# moscow_esp8266_revb.net
KiCad netlist of a schematic drawn in EAGLE
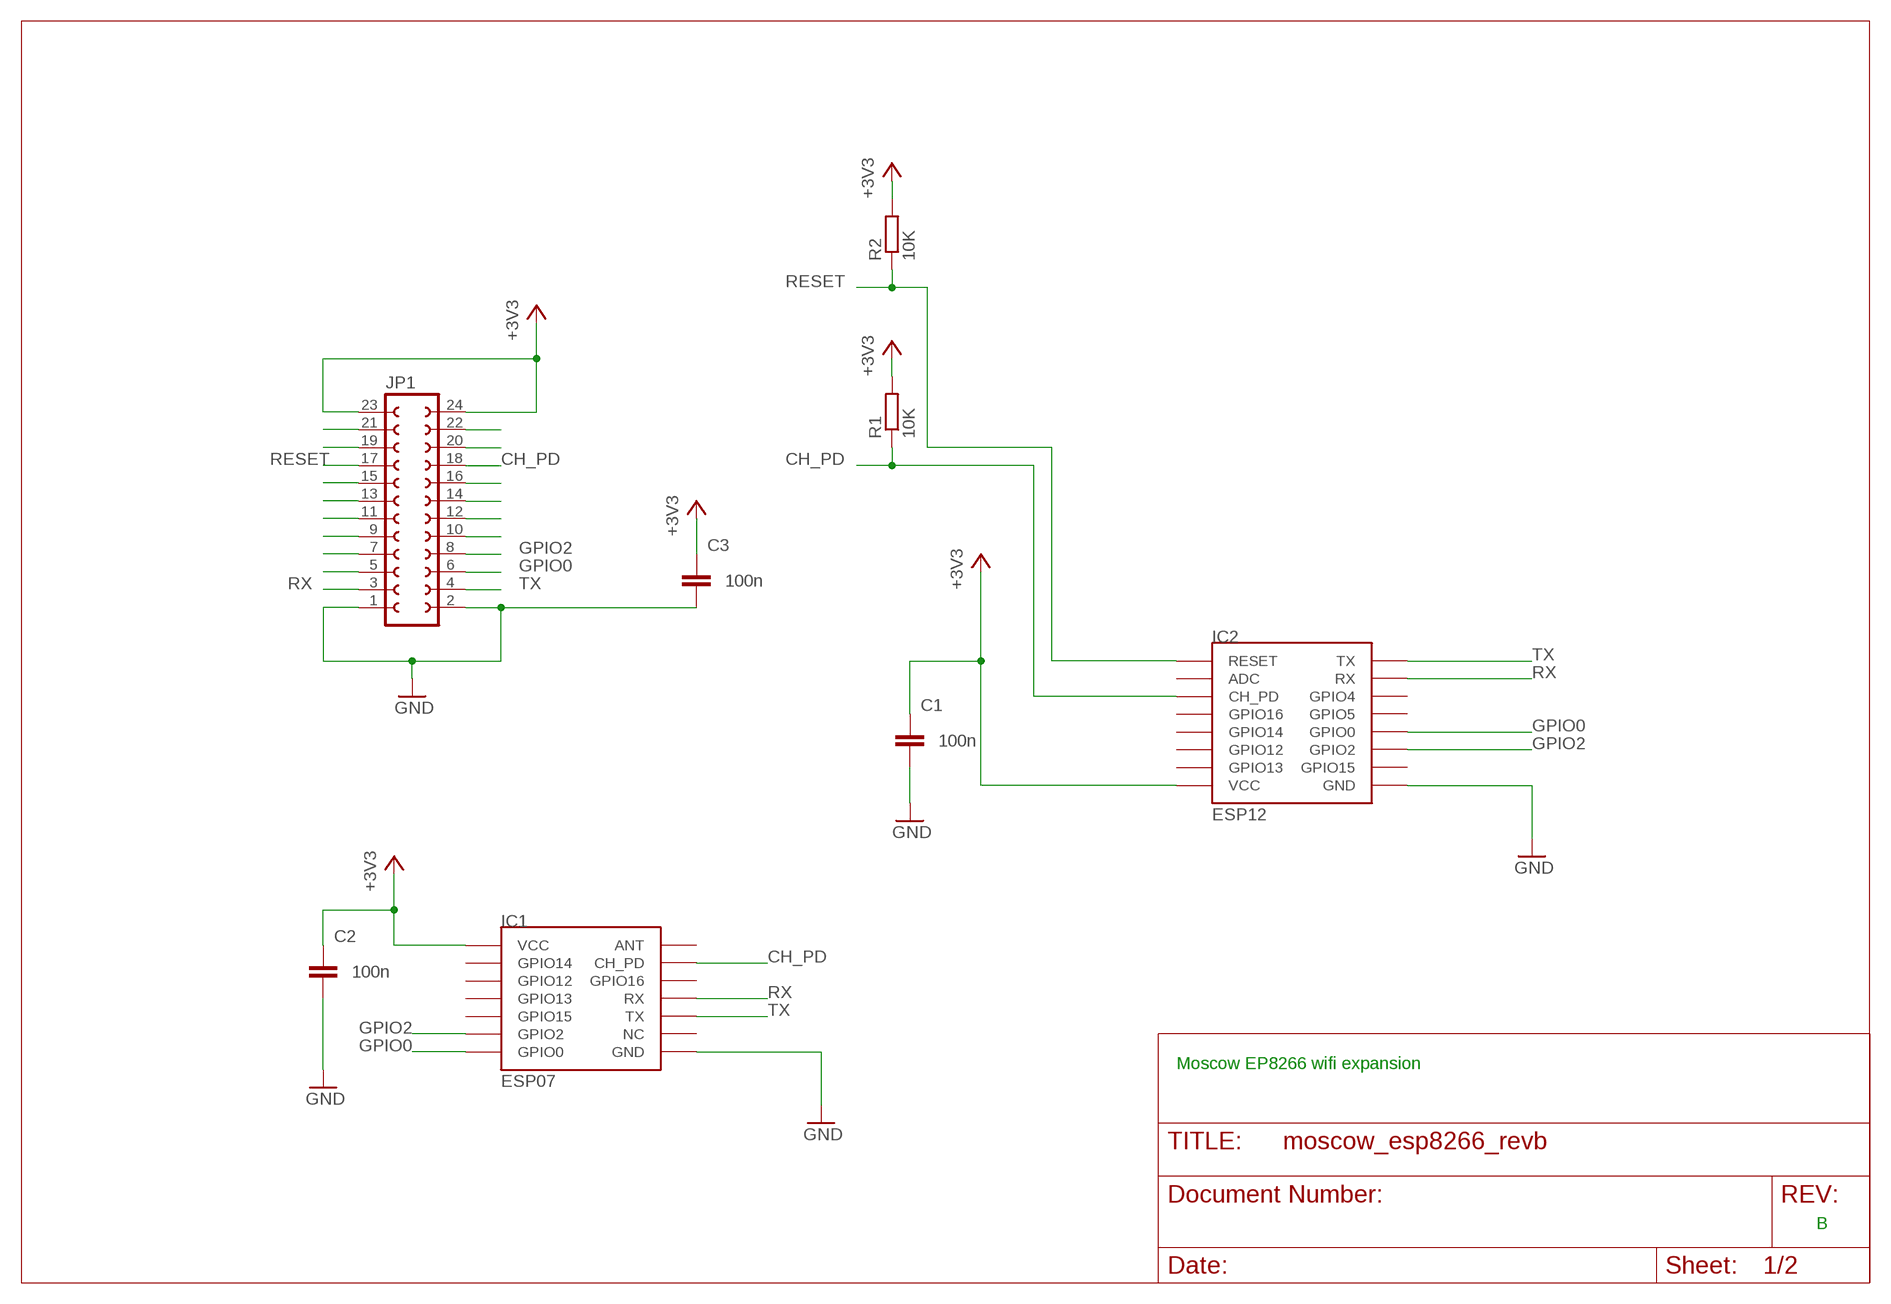
[diagram p0: schematic, sheet 1]
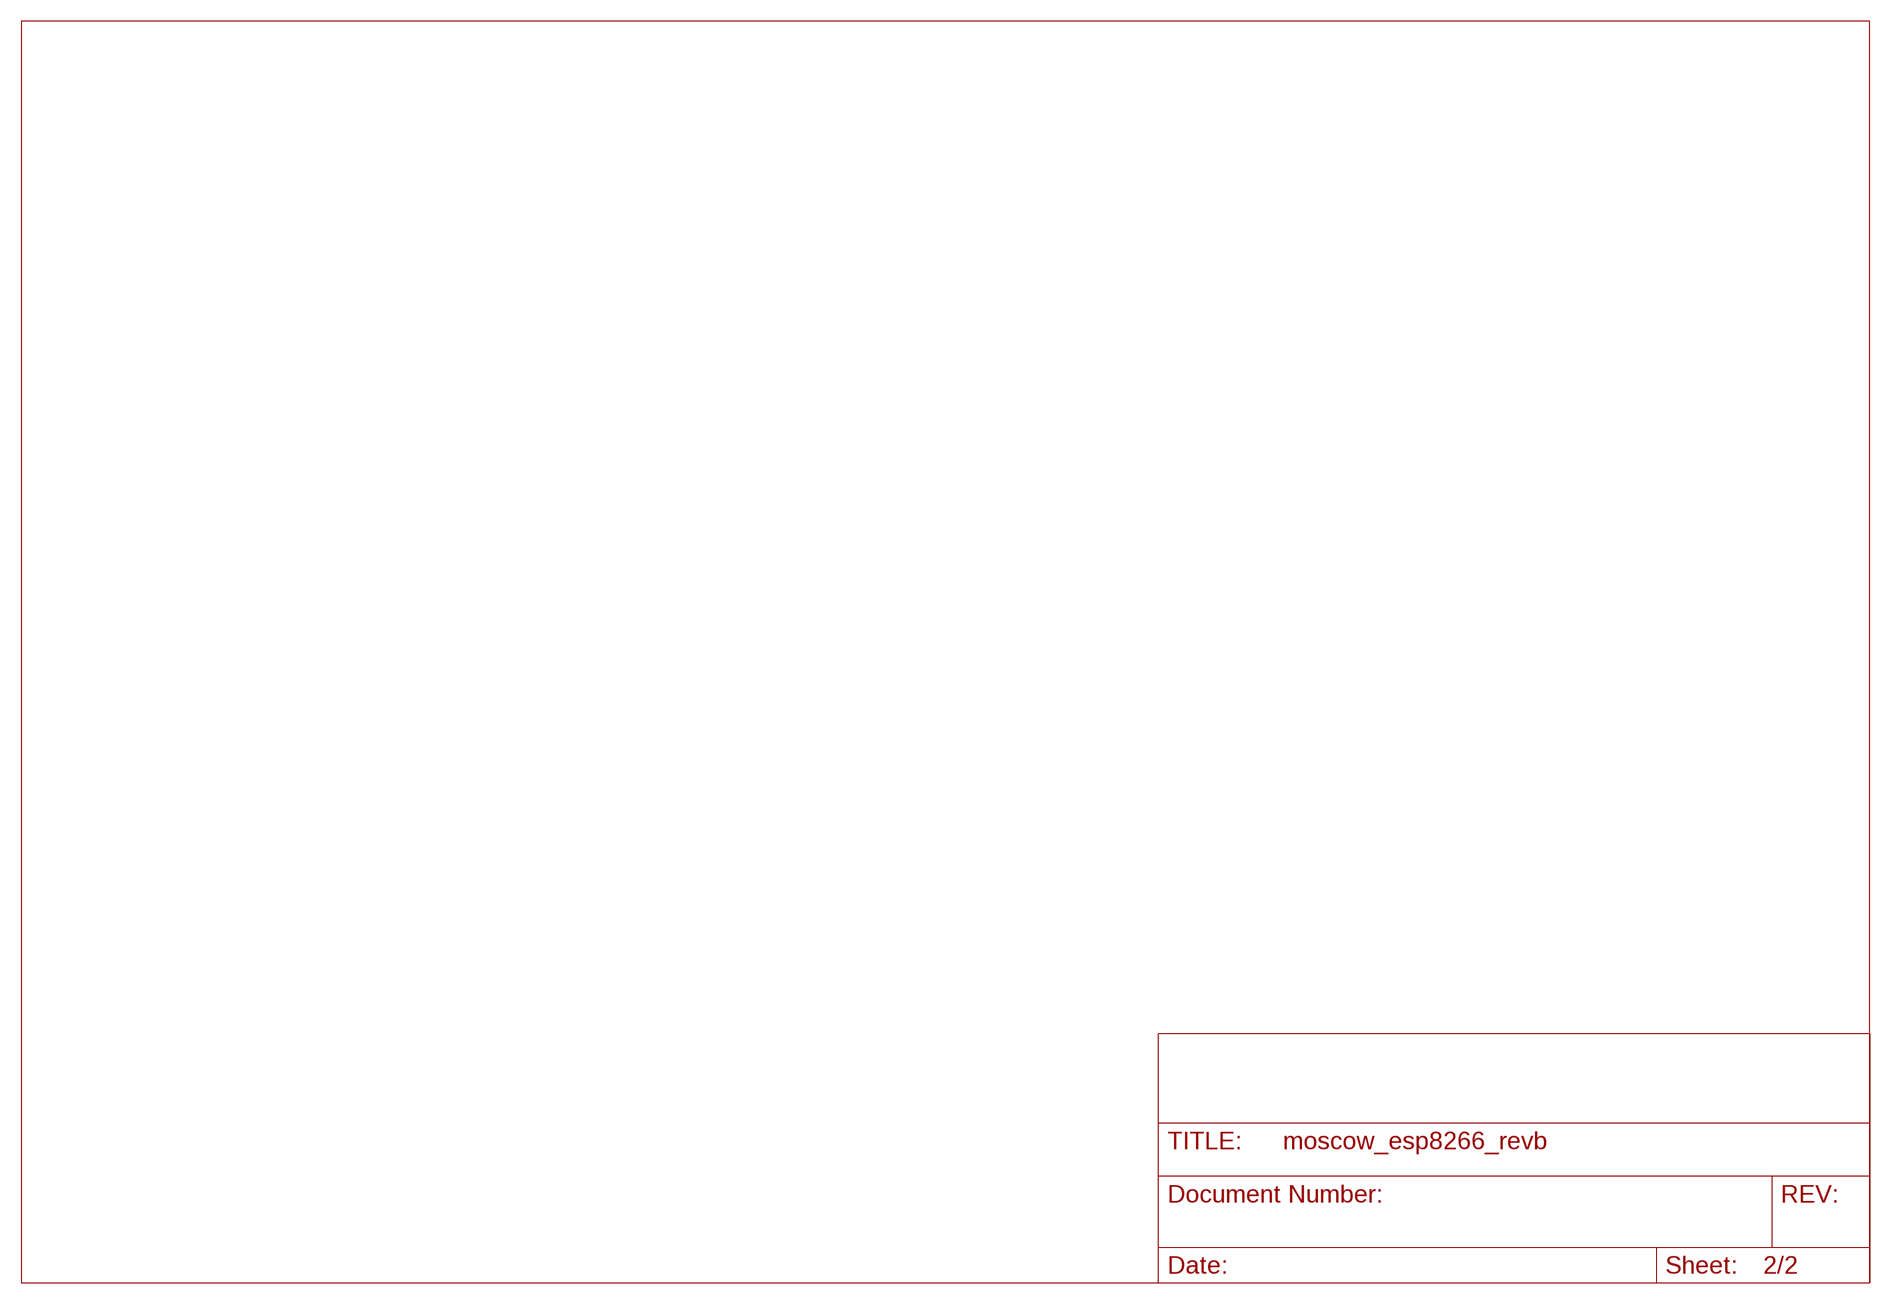
[diagram p1: schematic, sheet 2]

(export (version "E")
  (design (tool "Eeschema 10.0.6"))
  (components
    (comp (ref "C1")
      (value "100n")
      (footprint "eagle-import:C0805")
      (libsource (lib "eagle-import") (part "C-EUC0805"))
    )
    (comp (ref "C2")
      (value "100n")
      (footprint "eagle-import:C0805")
      (libsource (lib "eagle-import") (part "C-EUC0805"))
    )
    (comp (ref "C3")
      (value "100n")
      (footprint "eagle-import:C0805")
      (libsource (lib "eagle-import") (part "C-EUC0805"))
    )
    (comp (ref "IC1")
      (value "ESP07")
      (footprint "eagle-import:ESP07")
      (libsource (lib "eagle-import") (part "ESP07"))
    )
    (comp (ref "IC2")
      (value "ESP12")
      (footprint "eagle-import:ESP12")
      (libsource (lib "eagle-import") (part "ESP12"))
    )
    (comp (ref "JP1")
      (value "FE12-2")
      (footprint "eagle-import:FE12-2")
      (libsource (lib "eagle-import") (part "FE12-2"))
    )
    (comp (ref "R1")
      (value "10K")
      (footprint "eagle-import:R0805")
      (libsource (lib "eagle-import") (part "R-EU_R0805"))
    )
    (comp (ref "R2")
      (value "10K")
      (footprint "eagle-import:R0805")
      (libsource (lib "eagle-import") (part "R-EU_R0805"))
    )
  )
  (nets
    (net (code "1") (name "+3V3") (class "Default")
      (node (ref "C1") (pin "1") (pinfunction "1_1") (pintype "passive"))
      (node (ref "C2") (pin "1") (pinfunction "1_1") (pintype "passive"))
      (node (ref "C3") (pin "1") (pinfunction "1_1") (pintype "passive"))
      (node (ref "IC1") (pin "VCC") (pinfunction "VCC_VCC") (pintype "bidirectional"))
      (node (ref "IC2") (pin "VCC") (pinfunction "VCC_VCC") (pintype "bidirectional"))
      (node (ref "JP1") (pin "23") (pinfunction "23_23") (pintype "passive"))
      (node (ref "JP1") (pin "24") (pinfunction "24_24") (pintype "passive"))
      (node (ref "R1") (pin "2") (pinfunction "2_2") (pintype "passive"))
      (node (ref "R2") (pin "2") (pinfunction "2_2") (pintype "passive"))
    )
    (net (code "2") (name "CH_PD") (class "Default")
      (node (ref "IC1") (pin "CH_PD") (pinfunction "CH_PD_CH_PD") (pintype "bidirectional"))
      (node (ref "IC2") (pin "CH_PD") (pinfunction "CH_PD_CH_PD") (pintype "bidirectional"))
      (node (ref "JP1") (pin "18") (pinfunction "18_18") (pintype "passive"))
      (node (ref "R1") (pin "1") (pinfunction "1_1") (pintype "passive"))
    )
    (net (code "3") (name "GND") (class "Default")
      (node (ref "C1") (pin "2") (pinfunction "2_2") (pintype "passive"))
      (node (ref "C2") (pin "2") (pinfunction "2_2") (pintype "passive"))
      (node (ref "C3") (pin "2") (pinfunction "2_2") (pintype "passive"))
      (node (ref "IC1") (pin "GND") (pinfunction "GND_GND") (pintype "bidirectional"))
      (node (ref "IC2") (pin "GND") (pinfunction "GND_GND") (pintype "bidirectional"))
      (node (ref "JP1") (pin "1") (pinfunction "1_1") (pintype "passive"))
      (node (ref "JP1") (pin "2") (pinfunction "2_2") (pintype "passive"))
    )
    (net (code "4") (name "GPIO0") (class "Default")
      (node (ref "IC1") (pin "GPIO0") (pinfunction "GPIO0_GPIO0") (pintype "bidirectional"))
      (node (ref "IC2") (pin "GPIO0") (pinfunction "GPIO0_GPIO0") (pintype "bidirectional"))
      (node (ref "JP1") (pin "6") (pinfunction "6_6") (pintype "passive"))
    )
    (net (code "5") (name "GPIO2") (class "Default")
      (node (ref "IC1") (pin "GPIO2") (pinfunction "GPIO2_GPIO2") (pintype "bidirectional"))
      (node (ref "IC2") (pin "GPIO2") (pinfunction "GPIO2_GPIO2") (pintype "bidirectional"))
      (node (ref "JP1") (pin "8") (pinfunction "8_8") (pintype "passive"))
    )
    (net (code "6") (name "RESET") (class "Default")
      (node (ref "IC2") (pin "RESET") (pinfunction "RESET_RESET") (pintype "bidirectional"))
      (node (ref "JP1") (pin "17") (pinfunction "17_17") (pintype "passive"))
      (node (ref "R2") (pin "1") (pinfunction "1_1") (pintype "passive"))
    )
    (net (code "7") (name "RX") (class "Default")
      (node (ref "IC1") (pin "RX") (pinfunction "RX_RX") (pintype "bidirectional"))
      (node (ref "IC2") (pin "RX") (pinfunction "RX_RX") (pintype "bidirectional"))
      (node (ref "JP1") (pin "3") (pinfunction "3_3") (pintype "passive"))
    )
    (net (code "8") (name "TX") (class "Default")
      (node (ref "IC1") (pin "TX") (pinfunction "TX_TX") (pintype "bidirectional"))
      (node (ref "IC2") (pin "TX") (pinfunction "TX_TX") (pintype "bidirectional"))
      (node (ref "JP1") (pin "4") (pinfunction "4_4") (pintype "passive"))
    )
    (net (code "9") (name "unconnected-(IC1-PadANT)") (class "Default")
      (node (ref "IC1") (pin "ANT") (pinfunction "ANT_ANT") (pintype "bidirectional"))
    )
    (net (code "10") (name "unconnected-(IC1-PadGPIO12)") (class "Default")
      (node (ref "IC1") (pin "GPIO12") (pinfunction "GPIO12_GPIO12") (pintype "bidirectional"))
    )
    (net (code "11") (name "unconnected-(IC1-PadGPIO13)") (class "Default")
      (node (ref "IC1") (pin "GPIO13") (pinfunction "GPIO13_GPIO13") (pintype "bidirectional"))
    )
    (net (code "12") (name "unconnected-(IC1-PadGPIO14)") (class "Default")
      (node (ref "IC1") (pin "GPIO14") (pinfunction "GPIO14_GPIO14") (pintype "bidirectional"))
    )
    (net (code "13") (name "unconnected-(IC1-PadGPIO15)") (class "Default")
      (node (ref "IC1") (pin "GPIO15") (pinfunction "GPIO15_GPIO15") (pintype "bidirectional"))
    )
    (net (code "14") (name "unconnected-(IC1-PadGPIO16)") (class "Default")
      (node (ref "IC1") (pin "GPIO16") (pinfunction "GPIO16_GPIO16") (pintype "bidirectional"))
    )
    (net (code "15") (name "unconnected-(IC1-PadNC)") (class "Default")
      (node (ref "IC1") (pin "NC") (pinfunction "NC_NC") (pintype "bidirectional"))
    )
    (net (code "16") (name "unconnected-(IC2-PadADC)") (class "Default")
      (node (ref "IC2") (pin "ADC") (pinfunction "ADC_ADC") (pintype "bidirectional"))
    )
    (net (code "17") (name "unconnected-(IC2-PadGPIO4)") (class "Default")
      (node (ref "IC2") (pin "GPIO4") (pinfunction "GPIO4_GPIO4") (pintype "bidirectional"))
    )
    (net (code "18") (name "unconnected-(IC2-PadGPIO5)") (class "Default")
      (node (ref "IC2") (pin "GPIO5") (pinfunction "GPIO5_GPIO5") (pintype "bidirectional"))
    )
    (net (code "19") (name "unconnected-(IC2-PadGPIO12)") (class "Default")
      (node (ref "IC2") (pin "GPIO12") (pinfunction "GPIO12_GPIO12") (pintype "bidirectional"))
    )
    (net (code "20") (name "unconnected-(IC2-PadGPIO13)") (class "Default")
      (node (ref "IC2") (pin "GPIO13") (pinfunction "GPIO13_GPIO13") (pintype "bidirectional"))
    )
    (net (code "21") (name "unconnected-(IC2-PadGPIO14)") (class "Default")
      (node (ref "IC2") (pin "GPIO14") (pinfunction "GPIO14_GPIO14") (pintype "bidirectional"))
    )
    (net (code "22") (name "unconnected-(IC2-PadGPIO15)") (class "Default")
      (node (ref "IC2") (pin "GPIO15") (pinfunction "GPIO15_GPIO15") (pintype "bidirectional"))
    )
    (net (code "23") (name "unconnected-(IC2-PadGPIO16)") (class "Default")
      (node (ref "IC2") (pin "GPIO16") (pinfunction "GPIO16_GPIO16") (pintype "bidirectional"))
    )
    (net (code "24") (name "unconnected-(JP1-Pad5)") (class "Default")
      (node (ref "JP1") (pin "5") (pinfunction "5_5") (pintype "passive"))
    )
    (net (code "25") (name "unconnected-(JP1-Pad7)") (class "Default")
      (node (ref "JP1") (pin "7") (pinfunction "7_7") (pintype "passive"))
    )
    (net (code "26") (name "unconnected-(JP1-Pad9)") (class "Default")
      (node (ref "JP1") (pin "9") (pinfunction "9_9") (pintype "passive"))
    )
    (net (code "27") (name "unconnected-(JP1-Pad10)") (class "Default")
      (node (ref "JP1") (pin "10") (pinfunction "10_10") (pintype "passive"))
    )
    (net (code "28") (name "unconnected-(JP1-Pad11)") (class "Default")
      (node (ref "JP1") (pin "11") (pinfunction "11_11") (pintype "passive"))
    )
    (net (code "29") (name "unconnected-(JP1-Pad12)") (class "Default")
      (node (ref "JP1") (pin "12") (pinfunction "12_12") (pintype "passive"))
    )
    (net (code "30") (name "unconnected-(JP1-Pad13)") (class "Default")
      (node (ref "JP1") (pin "13") (pinfunction "13_13") (pintype "passive"))
    )
    (net (code "31") (name "unconnected-(JP1-Pad14)") (class "Default")
      (node (ref "JP1") (pin "14") (pinfunction "14_14") (pintype "passive"))
    )
    (net (code "32") (name "unconnected-(JP1-Pad15)") (class "Default")
      (node (ref "JP1") (pin "15") (pinfunction "15_15") (pintype "passive"))
    )
    (net (code "33") (name "unconnected-(JP1-Pad16)") (class "Default")
      (node (ref "JP1") (pin "16") (pinfunction "16_16") (pintype "passive"))
    )
    (net (code "34") (name "unconnected-(JP1-Pad19)") (class "Default")
      (node (ref "JP1") (pin "19") (pinfunction "19_19") (pintype "passive"))
    )
    (net (code "35") (name "unconnected-(JP1-Pad20)") (class "Default")
      (node (ref "JP1") (pin "20") (pinfunction "20_20") (pintype "passive"))
    )
    (net (code "36") (name "unconnected-(JP1-Pad21)") (class "Default")
      (node (ref "JP1") (pin "21") (pinfunction "21_21") (pintype "passive"))
    )
    (net (code "37") (name "unconnected-(JP1-Pad22)") (class "Default")
      (node (ref "JP1") (pin "22") (pinfunction "22_22") (pintype "passive"))
    )
  )
)
